# PassiveFilter.net
KiCad netlist of a schematic drawn in Altium Designer
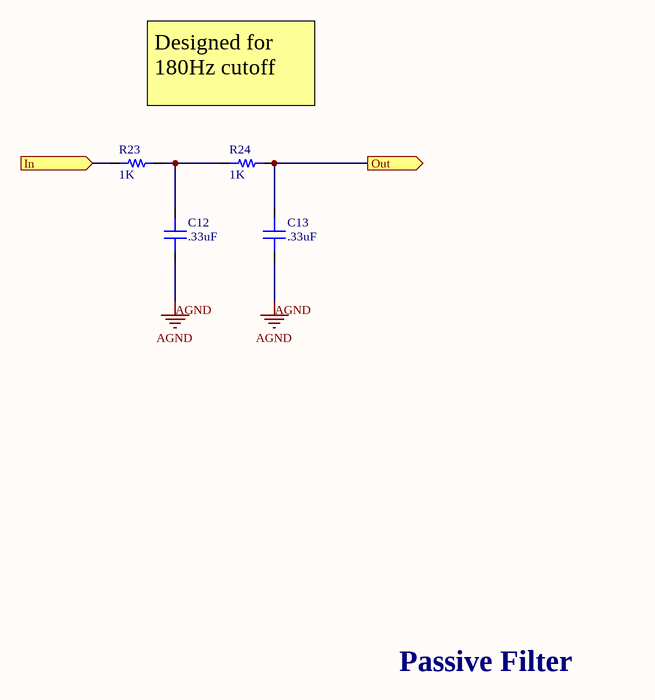
[diagram p0: PassiveFilter.SchDoc]

(export (version "E")
  (design (tool "Eeschema 10.0.6"))
  (components
    (comp (ref "C12")
      (value "capacitor")
      (footprint "0603")
      (description "Generic 0603 capacitor")
      (fields (field (name "CAPACITANCE") ".33uF") (field (name "VOLTAGE") "50"))
      (libsource (lib "altlib") (part "capacitor"))
    )
    (comp (ref "C13")
      (value "capacitor")
      (footprint "0603")
      (description "Generic 0603 capacitor")
      (fields (field (name "CAPACITANCE") ".33uF") (field (name "VOLTAGE") "50"))
      (libsource (lib "altlib") (part "capacitor"))
    )
    (comp (ref "R23")
      (value "resistor")
      (footprint "RES 0603/1608")
      (fields (field (name "RESISTANCE") "1K"))
      (libsource (lib "altlib") (part "resistor"))
    )
    (comp (ref "R24")
      (value "resistor")
      (footprint "RES 0603/1608")
      (fields (field (name "RESISTANCE") "1K"))
      (libsource (lib "altlib") (part "resistor"))
    )
  )
  (nets
    (net (code "1") (name "/In") (class "Default")
      (node (ref "R23") (pin "1") (pinfunction "1_1") (pintype "passive"))
    )
    (net (code "2") (name "/Out") (class "Default")
      (node (ref "C13") (pin "2") (pinfunction "2_2") (pintype "passive"))
      (node (ref "R24") (pin "2") (pinfunction "2_2") (pintype "passive"))
    )
    (net (code "3") (name "AGND") (class "Default")
      (node (ref "C12") (pin "1") (pinfunction "1_1") (pintype "passive"))
      (node (ref "C13") (pin "1") (pinfunction "1_1") (pintype "passive"))
    )
    (net (code "4") (name "Net-(C12-Pad2)") (class "Default")
      (node (ref "C12") (pin "2") (pinfunction "2_2") (pintype "passive"))
      (node (ref "R23") (pin "2") (pinfunction "2_2") (pintype "passive"))
      (node (ref "R24") (pin "1") (pinfunction "1_1") (pintype "passive"))
    )
  )
)
